# squematic2.net
KiCad netlist of a schematic drawn in EAGLE
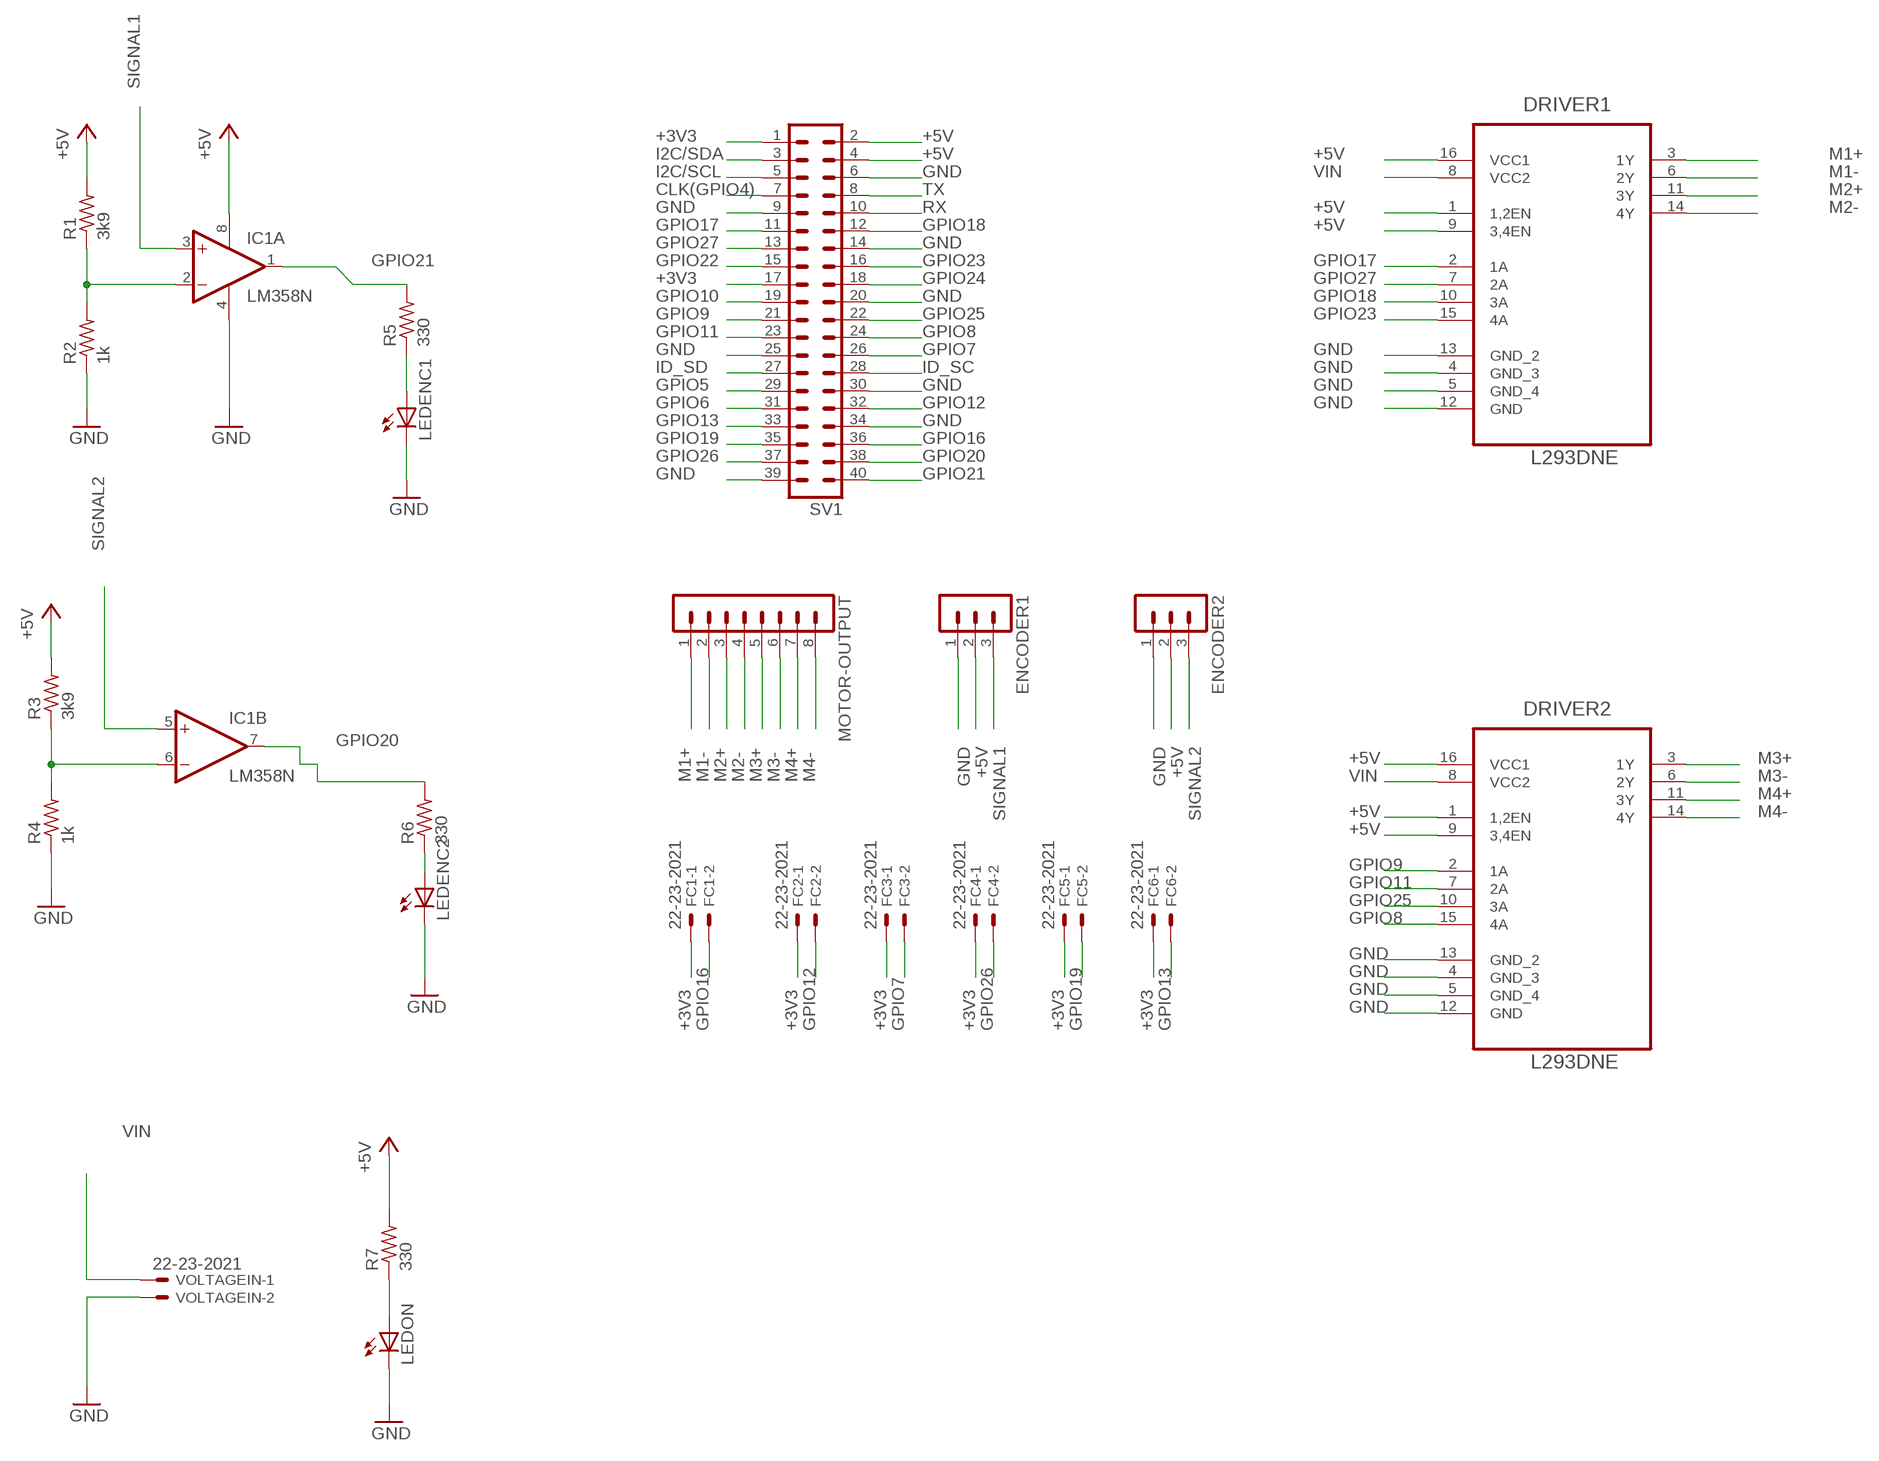
[diagram p0: schematic, sheet 1]

(export (version "E")
  (design (tool "Eeschema 10.0.6"))
  (components
    (comp (ref "DRIVER1")
      (value "L293DNE")
      (footprint "eagle-import:DIP254P762X508-16")
      (libsource (lib "eagle-import") (part "L293DNE"))
    )
    (comp (ref "DRIVER2")
      (value "L293DNE")
      (footprint "eagle-import:DIP254P762X508-16")
      (libsource (lib "eagle-import") (part "L293DNE"))
    )
    (comp (ref "ENCODER1")
      (value "MA03-1")
      (footprint "eagle-import:MA03-1")
      (libsource (lib "eagle-import") (part "MA03-1"))
    )
    (comp (ref "ENCODER2")
      (value "MA03-1")
      (footprint "eagle-import:MA03-1")
      (libsource (lib "eagle-import") (part "MA03-1"))
    )
    (comp (ref "FC1")
      (value "22-23-2021")
      (footprint "eagle-import:22-23-2021")
      (fields (field (name "MF") "MOLEX"))
      (libsource (lib "eagle-import") (part "22-23-2021"))
    )
    (comp (ref "FC2")
      (value "22-23-2021")
      (footprint "eagle-import:22-23-2021")
      (fields (field (name "MF") "MOLEX"))
      (libsource (lib "eagle-import") (part "22-23-2021"))
    )
    (comp (ref "FC3")
      (value "22-23-2021")
      (footprint "eagle-import:22-23-2021")
      (fields (field (name "MF") "MOLEX"))
      (libsource (lib "eagle-import") (part "22-23-2021"))
    )
    (comp (ref "FC4")
      (value "22-23-2021")
      (footprint "eagle-import:22-23-2021")
      (fields (field (name "MF") "MOLEX"))
      (libsource (lib "eagle-import") (part "22-23-2021"))
    )
    (comp (ref "FC5")
      (value "22-23-2021")
      (footprint "eagle-import:22-23-2021")
      (fields (field (name "MF") "MOLEX"))
      (libsource (lib "eagle-import") (part "22-23-2021"))
    )
    (comp (ref "FC6")
      (value "22-23-2021")
      (footprint "eagle-import:22-23-2021")
      (fields (field (name "MF") "MOLEX"))
      (libsource (lib "eagle-import") (part "22-23-2021"))
    )
    (comp (ref "IC1")
      (value "LM358N")
      (footprint "eagle-import:DIL08")
      (libsource (lib "eagle-import") (part "LM358N"))
    )
    (comp (ref "LEDENC1")
      (value "LED3MM")
      (footprint "eagle-import:LED3MM")
      (libsource (lib "eagle-import") (part "LED3MM"))
    )
    (comp (ref "LEDENC2")
      (value "LED3MM")
      (footprint "eagle-import:LED3MM")
      (libsource (lib "eagle-import") (part "LED3MM"))
    )
    (comp (ref "LEDON")
      (value "LED3MM")
      (footprint "eagle-import:LED3MM")
      (libsource (lib "eagle-import") (part "LED3MM"))
    )
    (comp (ref "MOTOR-OUTPUT")
      (value "MA08-1")
      (footprint "eagle-import:MA08-1")
      (libsource (lib "eagle-import") (part "MA08-1"))
    )
    (comp (ref "R1")
      (value "3k9")
      (footprint "eagle-import:0207_10")
      (libsource (lib "eagle-import") (part "R-US_0207/10"))
    )
    (comp (ref "R2")
      (value "1k")
      (footprint "eagle-import:0207_10")
      (libsource (lib "eagle-import") (part "R-US_0207/10"))
    )
    (comp (ref "R3")
      (value "3k9")
      (footprint "eagle-import:0207_10")
      (libsource (lib "eagle-import") (part "R-US_0207/10"))
    )
    (comp (ref "R4")
      (value "1k")
      (footprint "eagle-import:0207_10")
      (libsource (lib "eagle-import") (part "R-US_0207/10"))
    )
    (comp (ref "R5")
      (value "330")
      (footprint "eagle-import:0207_10")
      (libsource (lib "eagle-import") (part "R-US_0207/10"))
    )
    (comp (ref "R6")
      (value "330")
      (footprint "eagle-import:0207_10")
      (libsource (lib "eagle-import") (part "R-US_0207/10"))
    )
    (comp (ref "R7")
      (value "330")
      (footprint "eagle-import:0207_10")
      (libsource (lib "eagle-import") (part "R-US_0207/10"))
    )
    (comp (ref "SV1")
      (value "MA20-2")
      (footprint "eagle-import:MA20-2")
      (libsource (lib "eagle-import") (part "MA20-2"))
    )
    (comp (ref "VOLTAGEIN")
      (value "22-23-2021")
      (footprint "eagle-import:22-23-2021")
      (fields (field (name "MF") "MOLEX"))
      (libsource (lib "eagle-import") (part "22-23-2021"))
    )
  )
  (nets
    (net (code "1") (name "+5V") (class "Default")
      (node (ref "DRIVER1") (pin "1") (pinfunction "1,2EN_1") (pintype "input"))
      (node (ref "DRIVER1") (pin "16") (pinfunction "VCC1_16") (pintype "power_in"))
      (node (ref "DRIVER1") (pin "9") (pinfunction "3,4EN_9") (pintype "input"))
      (node (ref "DRIVER2") (pin "1") (pinfunction "1,2EN_1") (pintype "input"))
      (node (ref "DRIVER2") (pin "16") (pinfunction "VCC1_16") (pintype "power_in"))
      (node (ref "DRIVER2") (pin "9") (pinfunction "3,4EN_9") (pintype "input"))
      (node (ref "ENCODER1") (pin "2") (pinfunction "2_2") (pintype "passive"))
      (node (ref "ENCODER2") (pin "2") (pinfunction "2_2") (pintype "passive"))
      (node (ref "IC1") (pin "8") (pinfunction "V+_8") (pintype "power_in"))
      (node (ref "R1") (pin "2") (pinfunction "2_2") (pintype "passive"))
      (node (ref "R3") (pin "2") (pinfunction "2_2") (pintype "passive"))
      (node (ref "R7") (pin "2") (pinfunction "2_2") (pintype "passive"))
      (node (ref "SV1") (pin "2") (pinfunction "2_2") (pintype "passive"))
      (node (ref "SV1") (pin "4") (pinfunction "4_4") (pintype "passive"))
    )
    (net (code "2") (name "/+3V3") (class "Default")
      (node (ref "FC1") (pin "1") (pinfunction "S_1") (pintype "passive"))
      (node (ref "FC2") (pin "1") (pinfunction "S_1") (pintype "passive"))
      (node (ref "FC3") (pin "1") (pinfunction "S_1") (pintype "passive"))
      (node (ref "FC4") (pin "1") (pinfunction "S_1") (pintype "passive"))
      (node (ref "FC5") (pin "1") (pinfunction "S_1") (pintype "passive"))
      (node (ref "FC6") (pin "1") (pinfunction "S_1") (pintype "passive"))
      (node (ref "SV1") (pin "1") (pinfunction "1_1") (pintype "passive"))
      (node (ref "SV1") (pin "17") (pinfunction "17_17") (pintype "passive"))
    )
    (net (code "3") (name "/CLK(GPIO4)") (class "Default")
      (node (ref "SV1") (pin "7") (pinfunction "7_7") (pintype "passive"))
    )
    (net (code "4") (name "/GPIO5") (class "Default")
      (node (ref "SV1") (pin "29") (pinfunction "29_29") (pintype "passive"))
    )
    (net (code "5") (name "/GPIO6") (class "Default")
      (node (ref "SV1") (pin "31") (pinfunction "31_31") (pintype "passive"))
    )
    (net (code "6") (name "/GPIO7") (class "Default")
      (node (ref "FC3") (pin "2") (pinfunction "S_2") (pintype "passive"))
      (node (ref "SV1") (pin "26") (pinfunction "26_26") (pintype "passive"))
    )
    (net (code "7") (name "/GPIO8") (class "Default")
      (node (ref "DRIVER2") (pin "15") (pinfunction "4A_15") (pintype "input"))
      (node (ref "SV1") (pin "24") (pinfunction "24_24") (pintype "passive"))
    )
    (net (code "8") (name "/GPIO9") (class "Default")
      (node (ref "DRIVER2") (pin "2") (pinfunction "1A_2") (pintype "input"))
      (node (ref "SV1") (pin "21") (pinfunction "21_21") (pintype "passive"))
    )
    (net (code "9") (name "/GPIO10") (class "Default")
      (node (ref "SV1") (pin "19") (pinfunction "19_19") (pintype "passive"))
    )
    (net (code "10") (name "/GPIO11") (class "Default")
      (node (ref "DRIVER2") (pin "7") (pinfunction "2A_7") (pintype "input"))
      (node (ref "SV1") (pin "23") (pinfunction "23_23") (pintype "passive"))
    )
    (net (code "11") (name "/GPIO12") (class "Default")
      (node (ref "FC2") (pin "2") (pinfunction "S_2") (pintype "passive"))
      (node (ref "SV1") (pin "32") (pinfunction "32_32") (pintype "passive"))
    )
    (net (code "12") (name "/GPIO13") (class "Default")
      (node (ref "FC6") (pin "2") (pinfunction "S_2") (pintype "passive"))
      (node (ref "SV1") (pin "33") (pinfunction "33_33") (pintype "passive"))
    )
    (net (code "13") (name "/GPIO16") (class "Default")
      (node (ref "FC1") (pin "2") (pinfunction "S_2") (pintype "passive"))
      (node (ref "SV1") (pin "36") (pinfunction "36_36") (pintype "passive"))
    )
    (net (code "14") (name "/GPIO17") (class "Default")
      (node (ref "DRIVER1") (pin "2") (pinfunction "1A_2") (pintype "input"))
      (node (ref "SV1") (pin "11") (pinfunction "11_11") (pintype "passive"))
    )
    (net (code "15") (name "/GPIO18") (class "Default")
      (node (ref "DRIVER1") (pin "10") (pinfunction "3A_10") (pintype "input"))
      (node (ref "SV1") (pin "12") (pinfunction "12_12") (pintype "passive"))
    )
    (net (code "16") (name "/GPIO19") (class "Default")
      (node (ref "FC5") (pin "2") (pinfunction "S_2") (pintype "passive"))
      (node (ref "SV1") (pin "35") (pinfunction "35_35") (pintype "passive"))
    )
    (net (code "17") (name "/GPIO20") (class "Default")
      (node (ref "IC1") (pin "7") (pinfunction "OUT_7") (pintype "output"))
      (node (ref "R6") (pin "2") (pinfunction "2_2") (pintype "passive"))
      (node (ref "SV1") (pin "38") (pinfunction "38_38") (pintype "passive"))
    )
    (net (code "18") (name "/GPIO21") (class "Default")
      (node (ref "IC1") (pin "1") (pinfunction "OUT_1") (pintype "output"))
      (node (ref "R5") (pin "2") (pinfunction "2_2") (pintype "passive"))
      (node (ref "SV1") (pin "40") (pinfunction "40_40") (pintype "passive"))
    )
    (net (code "19") (name "/GPIO22") (class "Default")
      (node (ref "SV1") (pin "15") (pinfunction "15_15") (pintype "passive"))
    )
    (net (code "20") (name "/GPIO23") (class "Default")
      (node (ref "DRIVER1") (pin "15") (pinfunction "4A_15") (pintype "input"))
      (node (ref "SV1") (pin "16") (pinfunction "16_16") (pintype "passive"))
    )
    (net (code "21") (name "/GPIO24") (class "Default")
      (node (ref "SV1") (pin "18") (pinfunction "18_18") (pintype "passive"))
    )
    (net (code "22") (name "/GPIO25") (class "Default")
      (node (ref "DRIVER2") (pin "10") (pinfunction "3A_10") (pintype "input"))
      (node (ref "SV1") (pin "22") (pinfunction "22_22") (pintype "passive"))
    )
    (net (code "23") (name "/GPIO26") (class "Default")
      (node (ref "FC4") (pin "2") (pinfunction "S_2") (pintype "passive"))
      (node (ref "SV1") (pin "37") (pinfunction "37_37") (pintype "passive"))
    )
    (net (code "24") (name "/GPIO27") (class "Default")
      (node (ref "DRIVER1") (pin "7") (pinfunction "2A_7") (pintype "input"))
      (node (ref "SV1") (pin "13") (pinfunction "13_13") (pintype "passive"))
    )
    (net (code "25") (name "/I2C{slash}SCL") (class "Default")
      (node (ref "SV1") (pin "5") (pinfunction "5_5") (pintype "passive"))
    )
    (net (code "26") (name "/I2C{slash}SDA") (class "Default")
      (node (ref "SV1") (pin "3") (pinfunction "3_3") (pintype "passive"))
    )
    (net (code "27") (name "/ID_SC") (class "Default")
      (node (ref "SV1") (pin "28") (pinfunction "28_28") (pintype "passive"))
    )
    (net (code "28") (name "/ID_SD") (class "Default")
      (node (ref "SV1") (pin "27") (pinfunction "27_27") (pintype "passive"))
    )
    (net (code "29") (name "/M1+") (class "Default")
      (node (ref "DRIVER1") (pin "3") (pinfunction "1Y_3") (pintype "output"))
      (node (ref "MOTOR-OUTPUT") (pin "1") (pinfunction "1_1") (pintype "passive"))
    )
    (net (code "30") (name "/M1-") (class "Default")
      (node (ref "DRIVER1") (pin "6") (pinfunction "2Y_6") (pintype "output"))
      (node (ref "MOTOR-OUTPUT") (pin "2") (pinfunction "2_2") (pintype "passive"))
    )
    (net (code "31") (name "/M2+") (class "Default")
      (node (ref "DRIVER1") (pin "11") (pinfunction "3Y_11") (pintype "output"))
      (node (ref "MOTOR-OUTPUT") (pin "3") (pinfunction "3_3") (pintype "passive"))
    )
    (net (code "32") (name "/M2-") (class "Default")
      (node (ref "DRIVER1") (pin "14") (pinfunction "4Y_14") (pintype "output"))
      (node (ref "MOTOR-OUTPUT") (pin "4") (pinfunction "4_4") (pintype "passive"))
    )
    (net (code "33") (name "/M3+") (class "Default")
      (node (ref "DRIVER2") (pin "3") (pinfunction "1Y_3") (pintype "output"))
      (node (ref "MOTOR-OUTPUT") (pin "5") (pinfunction "5_5") (pintype "passive"))
    )
    (net (code "34") (name "/M3-") (class "Default")
      (node (ref "DRIVER2") (pin "6") (pinfunction "2Y_6") (pintype "output"))
      (node (ref "MOTOR-OUTPUT") (pin "6") (pinfunction "6_6") (pintype "passive"))
    )
    (net (code "35") (name "/M4+") (class "Default")
      (node (ref "DRIVER2") (pin "11") (pinfunction "3Y_11") (pintype "output"))
      (node (ref "MOTOR-OUTPUT") (pin "7") (pinfunction "7_7") (pintype "passive"))
    )
    (net (code "36") (name "/M4-") (class "Default")
      (node (ref "DRIVER2") (pin "14") (pinfunction "4Y_14") (pintype "output"))
      (node (ref "MOTOR-OUTPUT") (pin "8") (pinfunction "8_8") (pintype "passive"))
    )
    (net (code "37") (name "/RX") (class "Default")
      (node (ref "SV1") (pin "10") (pinfunction "10_10") (pintype "passive"))
    )
    (net (code "38") (name "/SIGNAL1") (class "Default")
      (node (ref "ENCODER1") (pin "3") (pinfunction "3_3") (pintype "passive"))
      (node (ref "IC1") (pin "3") (pinfunction "+IN_3") (pintype "input"))
    )
    (net (code "39") (name "/SIGNAL2") (class "Default")
      (node (ref "ENCODER2") (pin "3") (pinfunction "3_3") (pintype "passive"))
      (node (ref "IC1") (pin "5") (pinfunction "+IN_5") (pintype "input"))
    )
    (net (code "40") (name "/TX") (class "Default")
      (node (ref "SV1") (pin "8") (pinfunction "8_8") (pintype "passive"))
    )
    (net (code "41") (name "/VIN") (class "Default")
      (node (ref "DRIVER1") (pin "8") (pinfunction "VCC2_8") (pintype "power_in"))
      (node (ref "DRIVER2") (pin "8") (pinfunction "VCC2_8") (pintype "power_in"))
      (node (ref "VOLTAGEIN") (pin "1") (pinfunction "S_1") (pintype "passive"))
    )
    (net (code "42") (name "GND") (class "Default")
      (node (ref "DRIVER1") (pin "12") (pinfunction "GND_12") (pintype "passive"))
      (node (ref "DRIVER1") (pin "13") (pinfunction "GND_2_13") (pintype "passive"))
      (node (ref "DRIVER1") (pin "4") (pinfunction "GND_3_4") (pintype "passive"))
      (node (ref "DRIVER1") (pin "5") (pinfunction "GND_4_5") (pintype "passive"))
      (node (ref "DRIVER2") (pin "12") (pinfunction "GND_12") (pintype "passive"))
      (node (ref "DRIVER2") (pin "13") (pinfunction "GND_2_13") (pintype "passive"))
      (node (ref "DRIVER2") (pin "4") (pinfunction "GND_3_4") (pintype "passive"))
      (node (ref "DRIVER2") (pin "5") (pinfunction "GND_4_5") (pintype "passive"))
      (node (ref "ENCODER1") (pin "1") (pinfunction "1_1") (pintype "passive"))
      (node (ref "ENCODER2") (pin "1") (pinfunction "1_1") (pintype "passive"))
      (node (ref "IC1") (pin "4") (pinfunction "V-_4") (pintype "power_in"))
      (node (ref "LEDENC1") (pin "K") (pinfunction "C_K") (pintype "passive"))
      (node (ref "LEDENC2") (pin "K") (pinfunction "C_K") (pintype "passive"))
      (node (ref "LEDON") (pin "K") (pinfunction "C_K") (pintype "passive"))
      (node (ref "R2") (pin "1") (pinfunction "1_1") (pintype "passive"))
      (node (ref "R4") (pin "1") (pinfunction "1_1") (pintype "passive"))
      (node (ref "SV1") (pin "14") (pinfunction "14_14") (pintype "passive"))
      (node (ref "SV1") (pin "20") (pinfunction "20_20") (pintype "passive"))
      (node (ref "SV1") (pin "25") (pinfunction "25_25") (pintype "passive"))
      (node (ref "SV1") (pin "30") (pinfunction "30_30") (pintype "passive"))
      (node (ref "SV1") (pin "34") (pinfunction "34_34") (pintype "passive"))
      (node (ref "SV1") (pin "39") (pinfunction "39_39") (pintype "passive"))
      (node (ref "SV1") (pin "6") (pinfunction "6_6") (pintype "passive"))
      (node (ref "SV1") (pin "9") (pinfunction "9_9") (pintype "passive"))
      (node (ref "VOLTAGEIN") (pin "2") (pinfunction "S_2") (pintype "passive"))
    )
    (net (code "43") (name "Net-(IC1A--IN)") (class "Default")
      (node (ref "IC1") (pin "2") (pinfunction "-IN_2") (pintype "input"))
      (node (ref "R1") (pin "1") (pinfunction "1_1") (pintype "passive"))
      (node (ref "R2") (pin "2") (pinfunction "2_2") (pintype "passive"))
    )
    (net (code "44") (name "Net-(IC1B--IN)") (class "Default")
      (node (ref "IC1") (pin "6") (pinfunction "-IN_6") (pintype "input"))
      (node (ref "R3") (pin "1") (pinfunction "1_1") (pintype "passive"))
      (node (ref "R4") (pin "2") (pinfunction "2_2") (pintype "passive"))
    )
    (net (code "45") (name "Net-(LEDENC1-PadA)") (class "Default")
      (node (ref "LEDENC1") (pin "A") (pinfunction "A_A") (pintype "passive"))
      (node (ref "R5") (pin "1") (pinfunction "1_1") (pintype "passive"))
    )
    (net (code "46") (name "Net-(LEDENC2-PadA)") (class "Default")
      (node (ref "LEDENC2") (pin "A") (pinfunction "A_A") (pintype "passive"))
      (node (ref "R6") (pin "1") (pinfunction "1_1") (pintype "passive"))
    )
    (net (code "47") (name "Net-(LEDON-PadA)") (class "Default")
      (node (ref "LEDON") (pin "A") (pinfunction "A_A") (pintype "passive"))
      (node (ref "R7") (pin "1") (pinfunction "1_1") (pintype "passive"))
    )
  )
)
